# 1FA.net
KiCad netlist of a schematic drawn in EAGLE
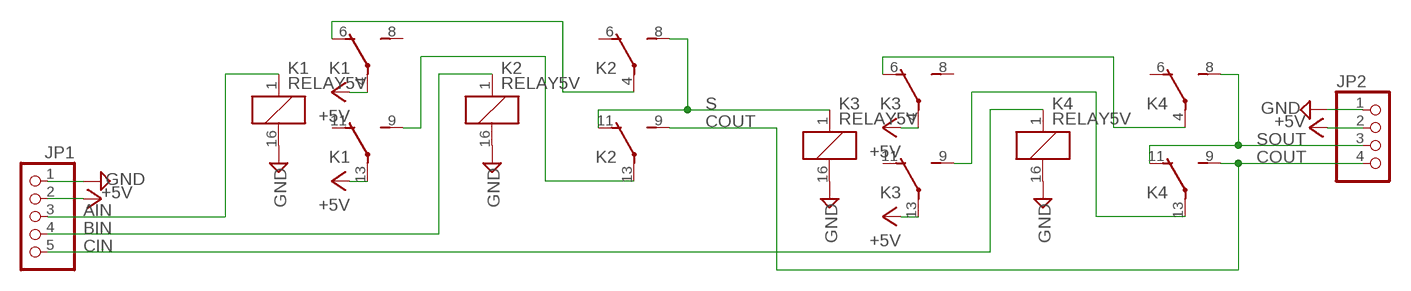
[diagram p0: schematic, sheet 1]

(export (version "E")
  (design (tool "Eeschema 10.0.6"))
  (components
    (comp (ref "JP1")
      (value "PINHD-1X5")
      (footprint "eagle-import:1X05")
      (libsource (lib "eagle-import") (part "PINHD-1X5"))
    )
    (comp (ref "JP2")
      (value "PINHD-1X4")
      (footprint "eagle-import:1X04")
      (libsource (lib "eagle-import") (part "PINHD-1X4"))
    )
    (comp (ref "K1")
      (value "RELAY5V")
      (footprint "eagle-import:DS-BT")
      (libsource (lib "eagle-import") (part "RELAY5V"))
    )
    (comp (ref "K2")
      (value "RELAY5V")
      (footprint "eagle-import:DS-BT")
      (libsource (lib "eagle-import") (part "RELAY5V"))
    )
    (comp (ref "K3")
      (value "RELAY5V")
      (footprint "eagle-import:DS-BT")
      (libsource (lib "eagle-import") (part "RELAY5V"))
    )
    (comp (ref "K4")
      (value "RELAY5V")
      (footprint "eagle-import:DS-BT")
      (libsource (lib "eagle-import") (part "RELAY5V"))
    )
  )
  (nets
    (net (code "1") (name "+5V") (class "Default")
      (node (ref "JP1") (pin "2") (pinfunction "2_2") (pintype "passive"))
      (node (ref "JP2") (pin "2") (pinfunction "2_2") (pintype "passive"))
      (node (ref "K1") (pin "13") (pinfunction "P_13") (pintype "passive"))
      (node (ref "K1") (pin "4") (pinfunction "P_4") (pintype "passive"))
      (node (ref "K3") (pin "13") (pinfunction "P_13") (pintype "passive"))
      (node (ref "K3") (pin "4") (pinfunction "P_4") (pintype "passive"))
    )
    (net (code "2") (name "/AIN") (class "Default")
      (node (ref "JP1") (pin "3") (pinfunction "3_3") (pintype "passive"))
      (node (ref "K1") (pin "1") (pinfunction "+_1") (pintype "passive"))
    )
    (net (code "3") (name "/BIN") (class "Default")
      (node (ref "JP1") (pin "4") (pinfunction "4_4") (pintype "passive"))
      (node (ref "K2") (pin "1") (pinfunction "+_1") (pintype "passive"))
    )
    (net (code "4") (name "/CIN") (class "Default")
      (node (ref "JP1") (pin "5") (pinfunction "5_5") (pintype "passive"))
      (node (ref "K4") (pin "1") (pinfunction "+_1") (pintype "passive"))
    )
    (net (code "5") (name "/COUT") (class "Default")
      (node (ref "JP2") (pin "4") (pinfunction "4_4") (pintype "passive"))
      (node (ref "K2") (pin "9") (pinfunction "S_9") (pintype "passive"))
      (node (ref "K4") (pin "9") (pinfunction "S_9") (pintype "passive"))
    )
    (net (code "6") (name "/S") (class "Default")
      (node (ref "K2") (pin "11") (pinfunction "O_11") (pintype "passive"))
      (node (ref "K2") (pin "8") (pinfunction "S_8") (pintype "passive"))
      (node (ref "K3") (pin "1") (pinfunction "+_1") (pintype "passive"))
    )
    (net (code "7") (name "/SOUT") (class "Default")
      (node (ref "JP2") (pin "3") (pinfunction "3_3") (pintype "passive"))
      (node (ref "K4") (pin "11") (pinfunction "O_11") (pintype "passive"))
      (node (ref "K4") (pin "8") (pinfunction "S_8") (pintype "passive"))
    )
    (net (code "8") (name "GND") (class "Default")
      (node (ref "JP1") (pin "1") (pinfunction "1_1") (pintype "passive"))
      (node (ref "JP2") (pin "1") (pinfunction "1_1") (pintype "passive"))
      (node (ref "K1") (pin "16") (pinfunction "-_16") (pintype "passive"))
      (node (ref "K2") (pin "16") (pinfunction "-_16") (pintype "passive"))
      (node (ref "K3") (pin "16") (pinfunction "-_16") (pintype "passive"))
      (node (ref "K4") (pin "16") (pinfunction "-_16") (pintype "passive"))
    )
    (net (code "9") (name "Net-(K1B-O)") (class "Default")
      (node (ref "K1") (pin "6") (pinfunction "O_6") (pintype "passive"))
      (node (ref "K2") (pin "4") (pinfunction "P_4") (pintype "passive"))
    )
    (net (code "10") (name "Net-(K1C-S)") (class "Default")
      (node (ref "K1") (pin "9") (pinfunction "S_9") (pintype "passive"))
      (node (ref "K2") (pin "13") (pinfunction "P_13") (pintype "passive"))
    )
    (net (code "11") (name "Net-(K3B-O)") (class "Default")
      (node (ref "K3") (pin "6") (pinfunction "O_6") (pintype "passive"))
      (node (ref "K4") (pin "4") (pinfunction "P_4") (pintype "passive"))
    )
    (net (code "12") (name "Net-(K3C-S)") (class "Default")
      (node (ref "K3") (pin "9") (pinfunction "S_9") (pintype "passive"))
      (node (ref "K4") (pin "13") (pinfunction "P_13") (pintype "passive"))
    )
    (net (code "13") (name "unconnected-(K1B-S-Pad8)") (class "Default")
      (node (ref "K1") (pin "8") (pinfunction "S_8") (pintype "passive"))
    )
    (net (code "14") (name "unconnected-(K1C-O-Pad11)") (class "Default")
      (node (ref "K1") (pin "11") (pinfunction "O_11") (pintype "passive"))
    )
    (net (code "15") (name "unconnected-(K2B-O-Pad6)") (class "Default")
      (node (ref "K2") (pin "6") (pinfunction "O_6") (pintype "passive"))
    )
    (net (code "16") (name "unconnected-(K3B-S-Pad8)") (class "Default")
      (node (ref "K3") (pin "8") (pinfunction "S_8") (pintype "passive"))
    )
    (net (code "17") (name "unconnected-(K3C-O-Pad11)") (class "Default")
      (node (ref "K3") (pin "11") (pinfunction "O_11") (pintype "passive"))
    )
    (net (code "18") (name "unconnected-(K4B-O-Pad6)") (class "Default")
      (node (ref "K4") (pin "6") (pinfunction "O_6") (pintype "passive"))
    )
  )
)
